# SCH_generic_ecu_diagram.net
KiCad netlist of a schematic drawn in EasyEDA
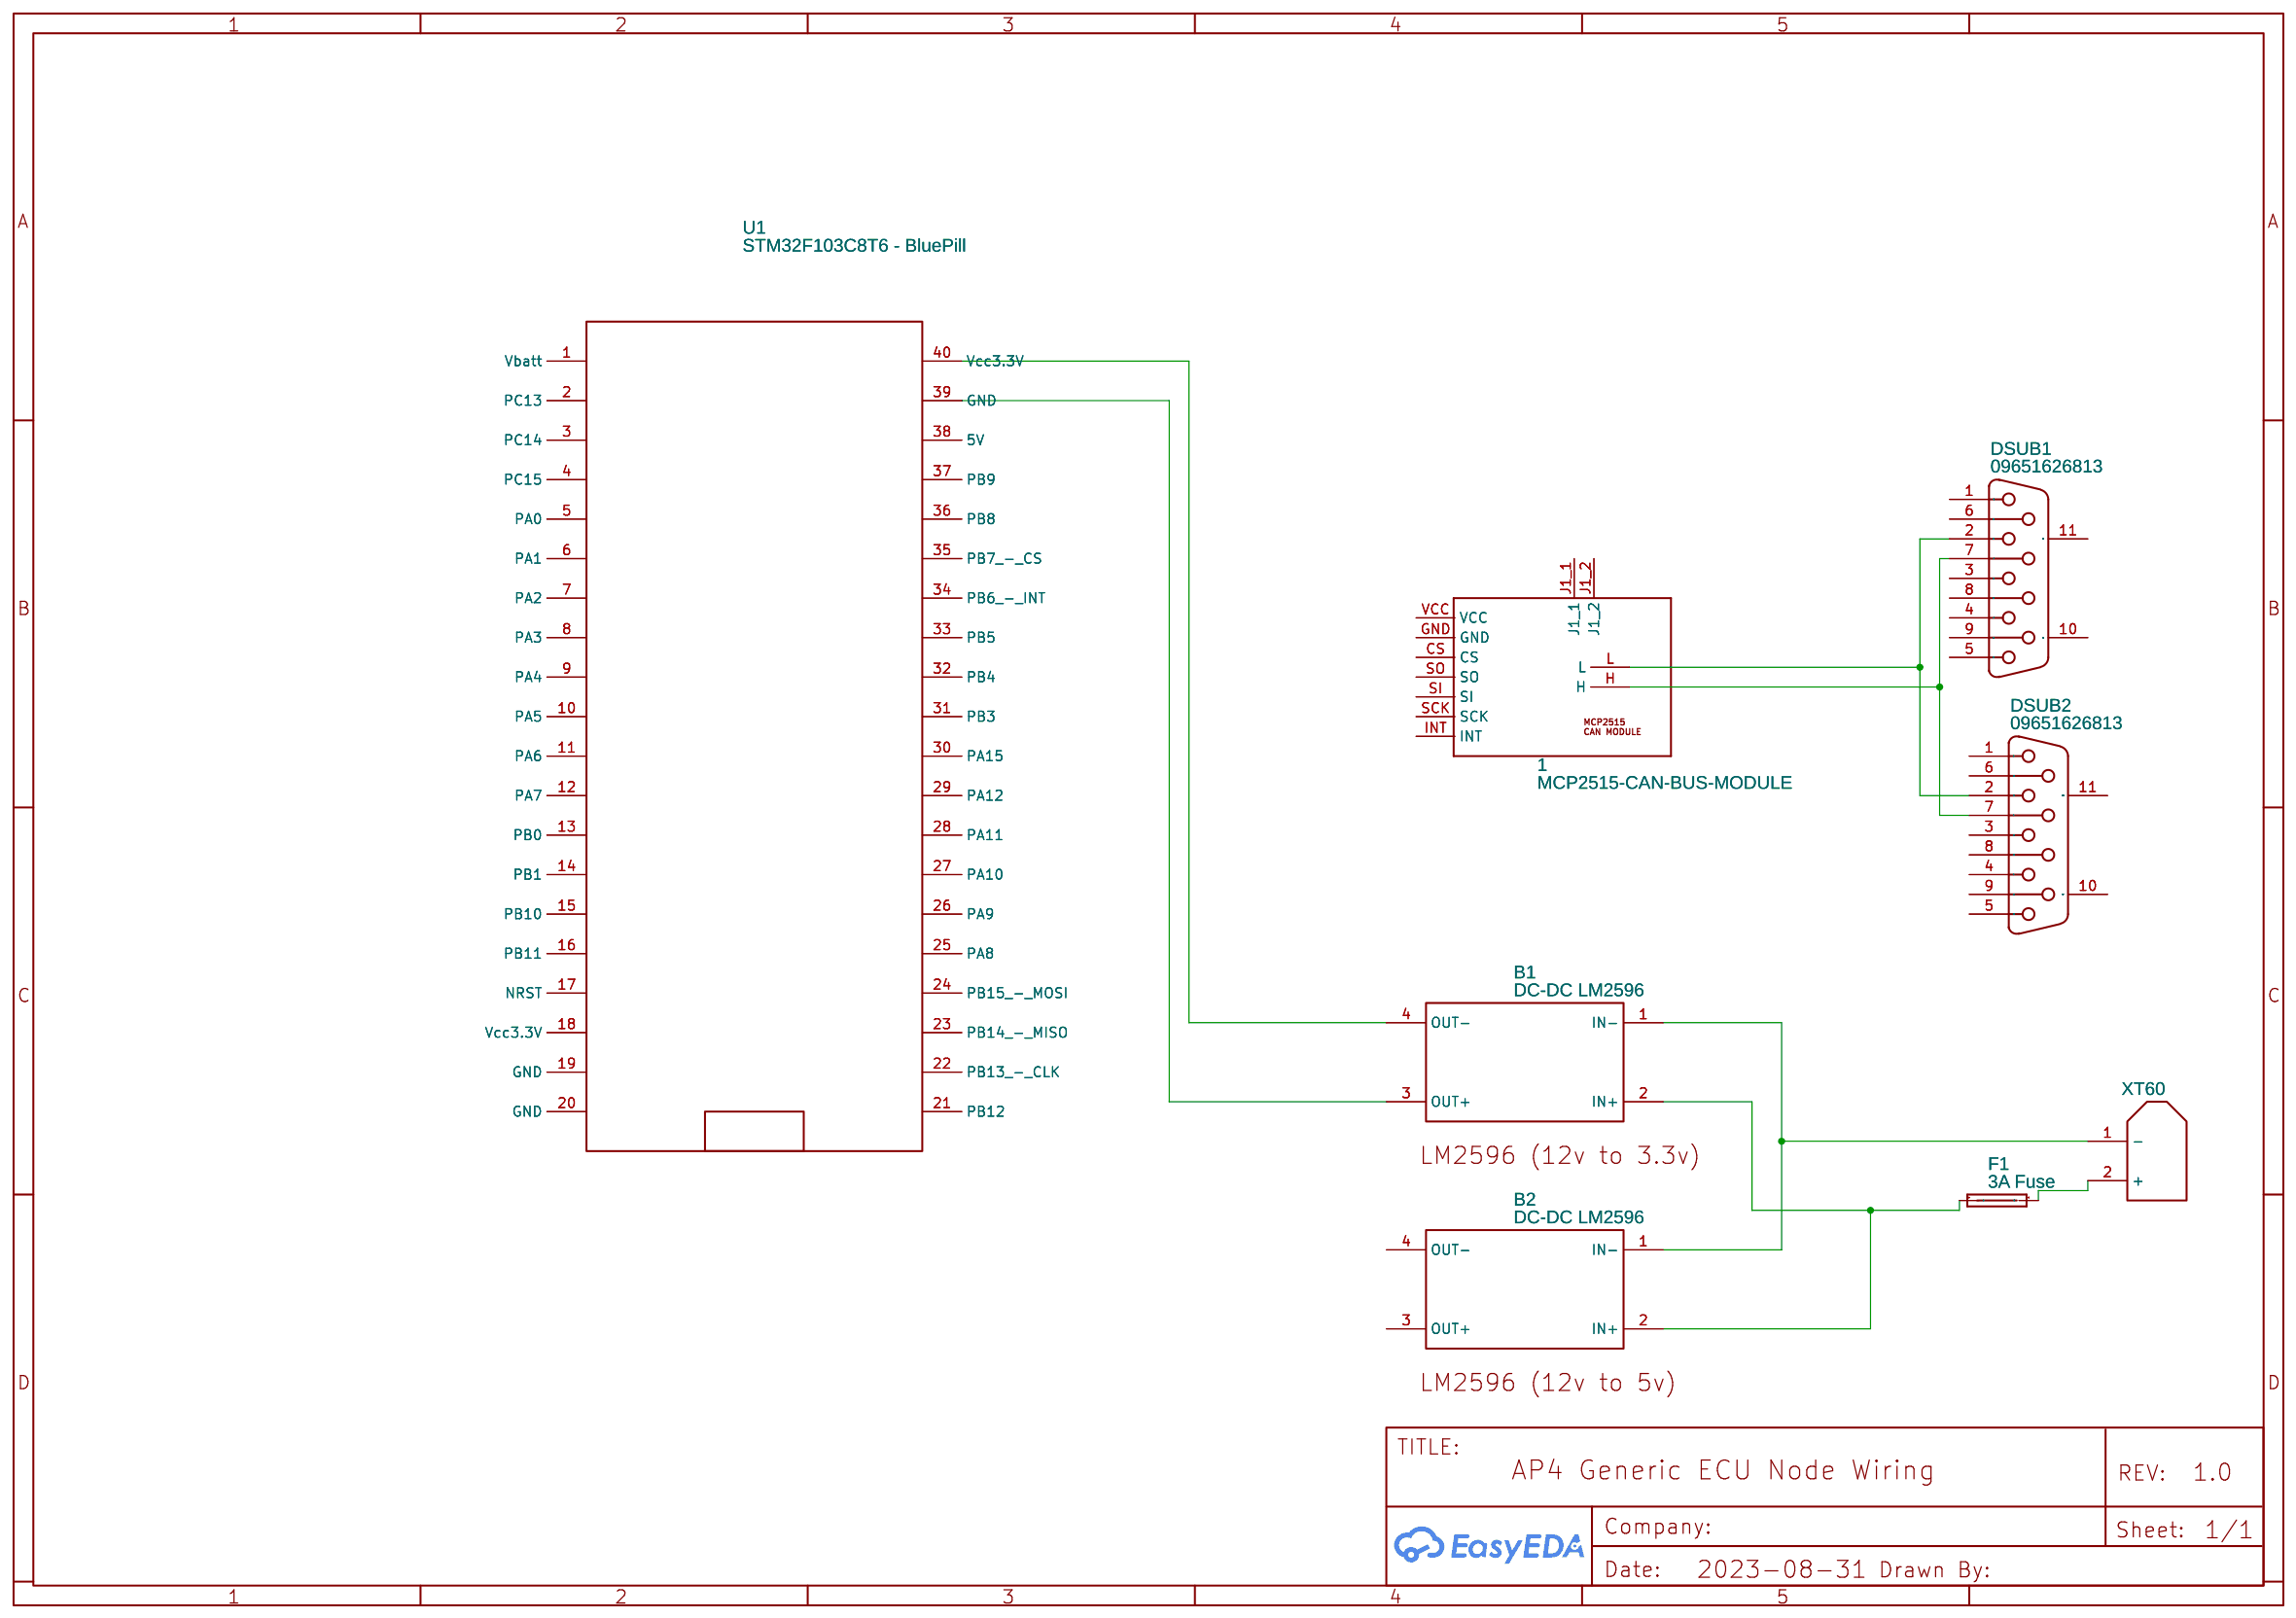
[diagram p0: schematic sheet]

(export (version "E")
  (design (tool "Eeschema 10.0.6"))
  (components
    (comp (ref "1") (value "MCP2515-CAN-BUS-MODULE") (libsource (lib "") (part "MCP2515-CAN-BUS-MODULE")))
    (comp (ref "B1")
      (value "DC-DC LM2596")
      (fields (field (name "Manufacturer Part") "New SchematicLib"))
      (libsource (lib "") (part "DC-DC LM2596"))
    )
    (comp (ref "B2")
      (value "DC-DC LM2596")
      (fields (field (name "Manufacturer Part") "New SchematicLib"))
      (libsource (lib "") (part "DC-DC LM2596_1"))
    )
    (comp (ref "DSUB1")
      (value "09651626813")
      (fields (field (name "Manufacturer") "Harting(浩亭)"))
      (libsource (lib "") (part "09651626813"))
    )
    (comp (ref "DSUB2")
      (value "09651626813")
      (fields (field (name "Manufacturer") "Harting(浩亭)"))
      (libsource (lib "") (part "09651626813"))
    )
    (comp (ref "F1") (value "3A Fuse") (libsource (lib "") (part "FUSE HOLDER WITH COVER FOR 5X20MM FUSE")))
    (comp (ref "NO")
      (value "XT60")
      (fields (field (name "Manufacturer") "AMASS"))
      (libsource (lib "") (part "XT60"))
    )
    (comp (ref "U1")
      (value "STM32F103C8T6 - BluePill")
      (fields (field (name "Manufacturer Part") "STM32Duino"))
      (libsource (lib "") (part "BluePill"))
    )
  )
  (nets
    (net (code "1") (name "Net-(1-PadH)") (class "Default")
      (node (ref "1") (pin "H") (pinfunction "H_H") (pintype "bidirectional"))
      (node (ref "DSUB1") (pin "7") (pinfunction "7_7") (pintype "input"))
      (node (ref "DSUB2") (pin "7") (pinfunction "7_7") (pintype "input"))
    )
    (net (code "2") (name "Net-(1-PadL)") (class "Default")
      (node (ref "1") (pin "L") (pinfunction "L_L") (pintype "bidirectional"))
      (node (ref "DSUB1") (pin "2") (pinfunction "2_2") (pintype "input"))
      (node (ref "DSUB2") (pin "2") (pinfunction "2_2") (pintype "input"))
    )
    (net (code "3") (name "Net-(B1-IN+)") (class "Default")
      (node (ref "B1") (pin "2") (pinfunction "IN+_2") (pintype "unspecified"))
      (node (ref "B2") (pin "2") (pinfunction "IN+_2") (pintype "unspecified"))
      (node (ref "F1") (pin "1") (pinfunction "1_1") (pintype "unspecified"))
    )
    (net (code "4") (name "Net-(B1-IN-)") (class "Default")
      (node (ref "B1") (pin "1") (pinfunction "IN-_1") (pintype "unspecified"))
      (node (ref "B2") (pin "1") (pinfunction "IN-_1") (pintype "unspecified"))
      (node (ref "NO") (pin "1") (pinfunction "-_1") (pintype "unspecified"))
    )
    (net (code "5") (name "Net-(NO-+)") (class "Default")
      (node (ref "F1") (pin "2") (pinfunction "2_2") (pintype "unspecified"))
      (node (ref "NO") (pin "2") (pinfunction "+_2") (pintype "unspecified"))
    )
    (net (code "6") (name "unconnected-(1-PadCS)") (class "Default")
      (node (ref "1") (pin "CS") (pinfunction "CS_CS") (pintype "bidirectional"))
    )
    (net (code "7") (name "unconnected-(1-PadGND)") (class "Default")
      (node (ref "1") (pin "GND") (pinfunction "GND_GND") (pintype "bidirectional"))
    )
    (net (code "8") (name "unconnected-(1-PadINT)") (class "Default")
      (node (ref "1") (pin "INT") (pinfunction "INT_INT") (pintype "bidirectional"))
    )
    (net (code "9") (name "unconnected-(1-PadJ1_1)") (class "Default")
      (node (ref "1") (pin "J1_1") (pinfunction "J1_1_J1_1") (pintype "bidirectional"))
    )
    (net (code "10") (name "unconnected-(1-PadJ1_2)") (class "Default")
      (node (ref "1") (pin "J1_2") (pinfunction "J1_2_J1_2") (pintype "bidirectional"))
    )
    (net (code "11") (name "unconnected-(1-PadSCK)") (class "Default")
      (node (ref "1") (pin "SCK") (pinfunction "SCK_SCK") (pintype "bidirectional"))
    )
    (net (code "12") (name "unconnected-(1-PadSI)") (class "Default")
      (node (ref "1") (pin "SI") (pinfunction "SI_SI") (pintype "bidirectional"))
    )
    (net (code "13") (name "unconnected-(1-PadSO)") (class "Default")
      (node (ref "1") (pin "SO") (pinfunction "SO_SO") (pintype "bidirectional"))
    )
    (net (code "14") (name "unconnected-(1-PadVCC)") (class "Default")
      (node (ref "1") (pin "VCC") (pinfunction "VCC_VCC") (pintype "bidirectional"))
    )
    (net (code "15") (name "unconnected-(B1-OUT+-Pad3)") (class "Default")
      (node (ref "B1") (pin "3") (pinfunction "OUT+_3") (pintype "unspecified"))
    )
    (net (code "16") (name "unconnected-(B1-OUT--Pad4)") (class "Default")
      (node (ref "B1") (pin "4") (pinfunction "OUT-_4") (pintype "unspecified"))
    )
    (net (code "17") (name "unconnected-(B2-OUT+-Pad3)") (class "Default")
      (node (ref "B2") (pin "3") (pinfunction "OUT+_3") (pintype "unspecified"))
    )
    (net (code "18") (name "unconnected-(B2-OUT--Pad4)") (class "Default")
      (node (ref "B2") (pin "4") (pinfunction "OUT-_4") (pintype "unspecified"))
    )
    (net (code "19") (name "unconnected-(DSUB1-MH1-Pad10)") (class "Default")
      (node (ref "DSUB1") (pin "10") (pinfunction "MH1_10") (pintype "input"))
    )
    (net (code "20") (name "unconnected-(DSUB1-MH2-Pad11)") (class "Default")
      (node (ref "DSUB1") (pin "11") (pinfunction "MH2_11") (pintype "input"))
    )
    (net (code "21") (name "unconnected-(DSUB1-Pad1)") (class "Default")
      (node (ref "DSUB1") (pin "1") (pinfunction "1_1") (pintype "input"))
    )
    (net (code "22") (name "unconnected-(DSUB1-Pad3)") (class "Default")
      (node (ref "DSUB1") (pin "3") (pinfunction "3_3") (pintype "input"))
    )
    (net (code "23") (name "unconnected-(DSUB1-Pad4)") (class "Default")
      (node (ref "DSUB1") (pin "4") (pinfunction "4_4") (pintype "input"))
    )
    (net (code "24") (name "unconnected-(DSUB1-Pad5)") (class "Default")
      (node (ref "DSUB1") (pin "5") (pinfunction "5_5") (pintype "input"))
    )
    (net (code "25") (name "unconnected-(DSUB1-Pad6)") (class "Default")
      (node (ref "DSUB1") (pin "6") (pinfunction "6_6") (pintype "input"))
    )
    (net (code "26") (name "unconnected-(DSUB1-Pad8)") (class "Default")
      (node (ref "DSUB1") (pin "8") (pinfunction "8_8") (pintype "input"))
    )
    (net (code "27") (name "unconnected-(DSUB1-Pad9)") (class "Default")
      (node (ref "DSUB1") (pin "9") (pinfunction "9_9") (pintype "input"))
    )
    (net (code "28") (name "unconnected-(DSUB2-MH1-Pad10)") (class "Default")
      (node (ref "DSUB2") (pin "10") (pinfunction "MH1_10") (pintype "input"))
    )
    (net (code "29") (name "unconnected-(DSUB2-MH2-Pad11)") (class "Default")
      (node (ref "DSUB2") (pin "11") (pinfunction "MH2_11") (pintype "input"))
    )
    (net (code "30") (name "unconnected-(DSUB2-Pad1)") (class "Default")
      (node (ref "DSUB2") (pin "1") (pinfunction "1_1") (pintype "input"))
    )
    (net (code "31") (name "unconnected-(DSUB2-Pad3)") (class "Default")
      (node (ref "DSUB2") (pin "3") (pinfunction "3_3") (pintype "input"))
    )
    (net (code "32") (name "unconnected-(DSUB2-Pad4)") (class "Default")
      (node (ref "DSUB2") (pin "4") (pinfunction "4_4") (pintype "input"))
    )
    (net (code "33") (name "unconnected-(DSUB2-Pad5)") (class "Default")
      (node (ref "DSUB2") (pin "5") (pinfunction "5_5") (pintype "input"))
    )
    (net (code "34") (name "unconnected-(DSUB2-Pad6)") (class "Default")
      (node (ref "DSUB2") (pin "6") (pinfunction "6_6") (pintype "input"))
    )
    (net (code "35") (name "unconnected-(DSUB2-Pad8)") (class "Default")
      (node (ref "DSUB2") (pin "8") (pinfunction "8_8") (pintype "input"))
    )
    (net (code "36") (name "unconnected-(DSUB2-Pad9)") (class "Default")
      (node (ref "DSUB2") (pin "9") (pinfunction "9_9") (pintype "input"))
    )
    (net (code "37") (name "unconnected-(U1-5V-Pad38)") (class "Default")
      (node (ref "U1") (pin "38") (pinfunction "5V_38") (pintype "unspecified"))
    )
    (net (code "38") (name "unconnected-(U1-GND-Pad19)") (class "Default")
      (node (ref "U1") (pin "19") (pinfunction "GND_19") (pintype "passive"))
    )
    (net (code "39") (name "unconnected-(U1-GND-Pad20)") (class "Default")
      (node (ref "U1") (pin "20") (pinfunction "GND_20") (pintype "passive"))
    )
    (net (code "40") (name "unconnected-(U1-GND-Pad39)") (class "Default")
      (node (ref "U1") (pin "39") (pinfunction "GND_39") (pintype "passive"))
    )
    (net (code "41") (name "unconnected-(U1-NRST-Pad17)") (class "Default")
      (node (ref "U1") (pin "17") (pinfunction "NRST_17") (pintype "unspecified"))
    )
    (net (code "42") (name "unconnected-(U1-PA0-Pad5)") (class "Default")
      (node (ref "U1") (pin "5") (pinfunction "PA0_5") (pintype "unspecified"))
    )
    (net (code "43") (name "unconnected-(U1-PA1-Pad6)") (class "Default")
      (node (ref "U1") (pin "6") (pinfunction "PA1_6") (pintype "unspecified"))
    )
    (net (code "44") (name "unconnected-(U1-PA2-Pad7)") (class "Default")
      (node (ref "U1") (pin "7") (pinfunction "PA2_7") (pintype "unspecified"))
    )
    (net (code "45") (name "unconnected-(U1-PA3-Pad8)") (class "Default")
      (node (ref "U1") (pin "8") (pinfunction "PA3_8") (pintype "unspecified"))
    )
    (net (code "46") (name "unconnected-(U1-PA4-Pad9)") (class "Default")
      (node (ref "U1") (pin "9") (pinfunction "PA4_9") (pintype "unspecified"))
    )
    (net (code "47") (name "unconnected-(U1-PA5-Pad10)") (class "Default")
      (node (ref "U1") (pin "10") (pinfunction "PA5_10") (pintype "unspecified"))
    )
    (net (code "48") (name "unconnected-(U1-PA6-Pad11)") (class "Default")
      (node (ref "U1") (pin "11") (pinfunction "PA6_11") (pintype "unspecified"))
    )
    (net (code "49") (name "unconnected-(U1-PA7-Pad12)") (class "Default")
      (node (ref "U1") (pin "12") (pinfunction "PA7_12") (pintype "unspecified"))
    )
    (net (code "50") (name "unconnected-(U1-PA8-Pad25)") (class "Default")
      (node (ref "U1") (pin "25") (pinfunction "PA8_25") (pintype "unspecified"))
    )
    (net (code "51") (name "unconnected-(U1-PA9-Pad26)") (class "Default")
      (node (ref "U1") (pin "26") (pinfunction "PA9_26") (pintype "unspecified"))
    )
    (net (code "52") (name "unconnected-(U1-PA10-Pad27)") (class "Default")
      (node (ref "U1") (pin "27") (pinfunction "PA10_27") (pintype "unspecified"))
    )
    (net (code "53") (name "unconnected-(U1-PA11-Pad28)") (class "Default")
      (node (ref "U1") (pin "28") (pinfunction "PA11_28") (pintype "unspecified"))
    )
    (net (code "54") (name "unconnected-(U1-PA12-Pad29)") (class "Default")
      (node (ref "U1") (pin "29") (pinfunction "PA12_29") (pintype "unspecified"))
    )
    (net (code "55") (name "unconnected-(U1-PA15-Pad30)") (class "Default")
      (node (ref "U1") (pin "30") (pinfunction "PA15_30") (pintype "unspecified"))
    )
    (net (code "56") (name "unconnected-(U1-PB0-Pad13)") (class "Default")
      (node (ref "U1") (pin "13") (pinfunction "PB0_13") (pintype "unspecified"))
    )
    (net (code "57") (name "unconnected-(U1-PB1-Pad14)") (class "Default")
      (node (ref "U1") (pin "14") (pinfunction "PB1_14") (pintype "unspecified"))
    )
    (net (code "58") (name "unconnected-(U1-PB3-Pad31)") (class "Default")
      (node (ref "U1") (pin "31") (pinfunction "PB3_31") (pintype "unspecified"))
    )
    (net (code "59") (name "unconnected-(U1-PB4-Pad32)") (class "Default")
      (node (ref "U1") (pin "32") (pinfunction "PB4_32") (pintype "unspecified"))
    )
    (net (code "60") (name "unconnected-(U1-PB5-Pad33)") (class "Default")
      (node (ref "U1") (pin "33") (pinfunction "PB5_33") (pintype "unspecified"))
    )
    (net (code "61") (name "unconnected-(U1-PB6_-_INT-Pad34)") (class "Default")
      (node (ref "U1") (pin "34") (pinfunction "PB6_-_INT_34") (pintype "unspecified"))
    )
    (net (code "62") (name "unconnected-(U1-PB7_-_CS-Pad35)") (class "Default")
      (node (ref "U1") (pin "35") (pinfunction "PB7_-_CS_35") (pintype "unspecified"))
    )
    (net (code "63") (name "unconnected-(U1-PB8-Pad36)") (class "Default")
      (node (ref "U1") (pin "36") (pinfunction "PB8_36") (pintype "unspecified"))
    )
    (net (code "64") (name "unconnected-(U1-PB9-Pad37)") (class "Default")
      (node (ref "U1") (pin "37") (pinfunction "PB9_37") (pintype "unspecified"))
    )
    (net (code "65") (name "unconnected-(U1-PB10-Pad15)") (class "Default")
      (node (ref "U1") (pin "15") (pinfunction "PB10_15") (pintype "unspecified"))
    )
    (net (code "66") (name "unconnected-(U1-PB11-Pad16)") (class "Default")
      (node (ref "U1") (pin "16") (pinfunction "PB11_16") (pintype "unspecified"))
    )
    (net (code "67") (name "unconnected-(U1-PB12-Pad21)") (class "Default")
      (node (ref "U1") (pin "21") (pinfunction "PB12_21") (pintype "unspecified"))
    )
    (net (code "68") (name "unconnected-(U1-PB13_-_CLK-Pad22)") (class "Default")
      (node (ref "U1") (pin "22") (pinfunction "PB13_-_CLK_22") (pintype "unspecified"))
    )
    (net (code "69") (name "unconnected-(U1-PB14_-_MISO-Pad23)") (class "Default")
      (node (ref "U1") (pin "23") (pinfunction "PB14_-_MISO_23") (pintype "unspecified"))
    )
    (net (code "70") (name "unconnected-(U1-PB15_-_MOSI-Pad24)") (class "Default")
      (node (ref "U1") (pin "24") (pinfunction "PB15_-_MOSI_24") (pintype "unspecified"))
    )
    (net (code "71") (name "unconnected-(U1-PC13-Pad2)") (class "Default")
      (node (ref "U1") (pin "2") (pinfunction "PC13_2") (pintype "unspecified"))
    )
    (net (code "72") (name "unconnected-(U1-PC14-Pad3)") (class "Default")
      (node (ref "U1") (pin "3") (pinfunction "PC14_3") (pintype "unspecified"))
    )
    (net (code "73") (name "unconnected-(U1-PC15-Pad4)") (class "Default")
      (node (ref "U1") (pin "4") (pinfunction "PC15_4") (pintype "unspecified"))
    )
    (net (code "74") (name "unconnected-(U1-Vbatt-Pad1)") (class "Default")
      (node (ref "U1") (pin "1") (pinfunction "Vbatt_1") (pintype "passive"))
    )
    (net (code "75") (name "unconnected-(U1-Vcc3.3V-Pad18)") (class "Default")
      (node (ref "U1") (pin "18") (pinfunction "Vcc3.3V_18") (pintype "passive"))
    )
    (net (code "76") (name "unconnected-(U1-Vcc3.3V-Pad40)") (class "Default")
      (node (ref "U1") (pin "40") (pinfunction "Vcc3.3V_40") (pintype "passive"))
    )
  )
)
